# sensor_module_base.net
KiCad netlist of a schematic drawn in EAGLE
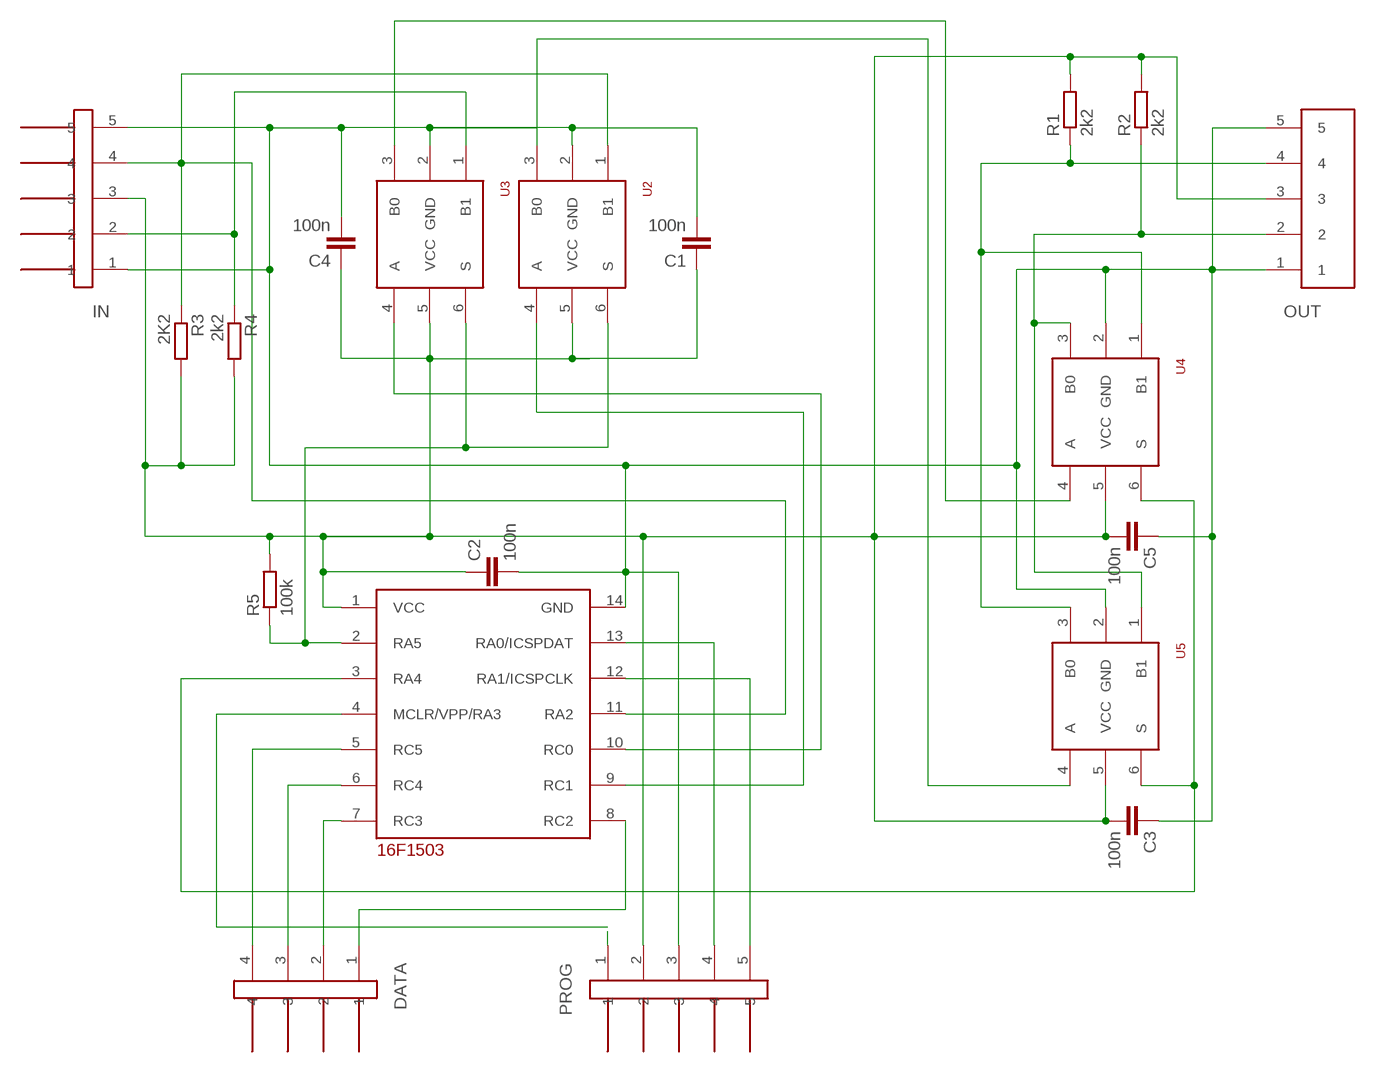
[diagram p0: schematic, sheet 1]

(export (version "E")
  (design (tool "Eeschema 10.0.6"))
  (components
    (comp (ref "C1")
      (value "100n")
      (footprint "eagle-import:C0603K")
      (libsource (lib "eagle-import") (part "C-EUC0603K"))
    )
    (comp (ref "C2")
      (value "100n")
      (footprint "eagle-import:C0603K")
      (libsource (lib "eagle-import") (part "C-EUC0603K"))
    )
    (comp (ref "C3")
      (value "100n")
      (footprint "eagle-import:C0603K")
      (libsource (lib "eagle-import") (part "C-EUC0603K"))
    )
    (comp (ref "C4")
      (value "100n")
      (footprint "eagle-import:C0603K")
      (libsource (lib "eagle-import") (part "C-EUC0603K"))
    )
    (comp (ref "C5")
      (value "100n")
      (footprint "eagle-import:C0603K")
      (libsource (lib "eagle-import") (part "C-EUC0603K"))
    )
    (comp (ref "DATA")
      (value "JUMPER4M")
      (footprint "eagle-import:JUMPER4M")
      (libsource (lib "eagle-import") (part "JUMPER4M"))
    )
    (comp (ref "IN")
      (value "JUMPER5M-90")
      (footprint "eagle-import:JUMPER5M-90")
      (libsource (lib "eagle-import") (part "JUMPER5M-90"))
    )
    (comp (ref "OUT")
      (value "JUMPER5F-90")
      (footprint "eagle-import:JUMPER5F-90")
      (libsource (lib "eagle-import") (part "JUMPER5F-90"))
    )
    (comp (ref "PROG")
      (value "JUMPER5M")
      (footprint "eagle-import:JUMPER5M")
      (libsource (lib "eagle-import") (part "JUMPER5M"))
    )
    (comp (ref "R1")
      (value "2k2")
      (footprint "eagle-import:R0603")
      (libsource (lib "eagle-import") (part "R-EU_R0603"))
    )
    (comp (ref "R2")
      (value "2k2")
      (footprint "eagle-import:R0603")
      (libsource (lib "eagle-import") (part "R-EU_R0603"))
    )
    (comp (ref "R3")
      (value "2K2")
      (footprint "eagle-import:R0603")
      (libsource (lib "eagle-import") (part "R-EU_R0603"))
    )
    (comp (ref "R4")
      (value "2k2")
      (footprint "eagle-import:R0603")
      (libsource (lib "eagle-import") (part "R-EU_R0603"))
    )
    (comp (ref "R5")
      (value "100k")
      (footprint "eagle-import:R0603")
      (libsource (lib "eagle-import") (part "R-EU_R0603"))
    )
    (comp (ref "U1")
      (value "16F103")
      (footprint "eagle-import:TSSOP14")
      (libsource (lib "eagle-import") (part "16F103-TSSOP"))
    )
    (comp (ref "U2")
      (value "NC7SB3157P6X")
      (footprint "eagle-import:SC70-6L")
      (libsource (lib "eagle-import") (part "NC7SB3157P6X"))
    )
    (comp (ref "U3")
      (value "NC7SB3157P6X")
      (footprint "eagle-import:SC70-6L")
      (libsource (lib "eagle-import") (part "NC7SB3157P6X"))
    )
    (comp (ref "U4")
      (value "NC7SB3157P6X")
      (footprint "eagle-import:SC70-6L")
      (libsource (lib "eagle-import") (part "NC7SB3157P6X"))
    )
    (comp (ref "U5")
      (value "NC7SB3157P6X")
      (footprint "eagle-import:SC70-6L")
      (libsource (lib "eagle-import") (part "NC7SB3157P6X"))
    )
  )
  (nets
    (net (code "1") (name "Net-(U1-GND)") (class "Default")
      (node (ref "C1") (pin "2") (pinfunction "2_2") (pintype "passive"))
      (node (ref "C2") (pin "2") (pinfunction "2_2") (pintype "passive"))
      (node (ref "C3") (pin "1") (pinfunction "1_1") (pintype "passive"))
      (node (ref "C4") (pin "2") (pinfunction "2_2") (pintype "passive"))
      (node (ref "C5") (pin "1") (pinfunction "1_1") (pintype "passive"))
      (node (ref "IN") (pin "1") (pinfunction "1_1") (pintype "bidirectional"))
      (node (ref "IN") (pin "5") (pinfunction "5_5") (pintype "bidirectional"))
      (node (ref "OUT") (pin "1") (pinfunction "1_1") (pintype "bidirectional"))
      (node (ref "OUT") (pin "5") (pinfunction "5_5") (pintype "bidirectional"))
      (node (ref "PROG") (pin "3") (pinfunction "3_3") (pintype "bidirectional"))
      (node (ref "U1") (pin "14") (pinfunction "GND_14") (pintype "power_in"))
      (node (ref "U2") (pin "2") (pinfunction "GND_2") (pintype "power_in"))
      (node (ref "U3") (pin "2") (pinfunction "GND_2") (pintype "power_in"))
      (node (ref "U4") (pin "2") (pinfunction "GND_2") (pintype "power_in"))
      (node (ref "U5") (pin "2") (pinfunction "GND_2") (pintype "power_in"))
    )
    (net (code "2") (name "Net-(U1-MCLR{slash}VPP{slash}RA3)") (class "Default")
      (node (ref "PROG") (pin "1") (pinfunction "1_1") (pintype "bidirectional"))
      (node (ref "U1") (pin "4") (pinfunction "MCLR/VPP/RA3_4") (pintype "bidirectional"))
    )
    (net (code "3") (name "Net-(U1-RA0{slash}ICSPDAT)") (class "Default")
      (node (ref "PROG") (pin "4") (pinfunction "4_4") (pintype "bidirectional"))
      (node (ref "U1") (pin "13") (pinfunction "RA0/ICSPDAT_13") (pintype "bidirectional"))
    )
    (net (code "4") (name "Net-(U1-RA1{slash}ICSPCLK)") (class "Default")
      (node (ref "PROG") (pin "5") (pinfunction "5_5") (pintype "bidirectional"))
      (node (ref "U1") (pin "12") (pinfunction "RA1/ICSPCLK_12") (pintype "bidirectional"))
    )
    (net (code "5") (name "Net-(U1-RA2)") (class "Default")
      (node (ref "IN") (pin "4") (pinfunction "4_4") (pintype "bidirectional"))
      (node (ref "R3") (pin "1") (pinfunction "1_1") (pintype "passive"))
      (node (ref "U1") (pin "11") (pinfunction "RA2_11") (pintype "bidirectional"))
      (node (ref "U2") (pin "1") (pinfunction "B1_1") (pintype "bidirectional"))
    )
    (net (code "6") (name "Net-(U1-RA4)") (class "Default")
      (node (ref "U1") (pin "3") (pinfunction "RA4_3") (pintype "bidirectional"))
      (node (ref "U4") (pin "6") (pinfunction "S_6") (pintype "bidirectional"))
      (node (ref "U5") (pin "6") (pinfunction "S_6") (pintype "bidirectional"))
    )
    (net (code "7") (name "Net-(U1-RA5)") (class "Default")
      (node (ref "R5") (pin "1") (pinfunction "1_1") (pintype "passive"))
      (node (ref "U1") (pin "2") (pinfunction "RA5_2") (pintype "bidirectional"))
      (node (ref "U2") (pin "6") (pinfunction "S_6") (pintype "bidirectional"))
      (node (ref "U3") (pin "6") (pinfunction "S_6") (pintype "bidirectional"))
    )
    (net (code "8") (name "Net-(U1-RC0)") (class "Default")
      (node (ref "U1") (pin "10") (pinfunction "RC0_10") (pintype "bidirectional"))
      (node (ref "U3") (pin "4") (pinfunction "A_4") (pintype "bidirectional"))
    )
    (net (code "9") (name "Net-(U1-RC1)") (class "Default")
      (node (ref "U1") (pin "9") (pinfunction "RC1_9") (pintype "bidirectional"))
      (node (ref "U2") (pin "4") (pinfunction "A_4") (pintype "bidirectional"))
    )
    (net (code "10") (name "Net-(U1-RC2)") (class "Default")
      (node (ref "DATA") (pin "1") (pinfunction "1_1") (pintype "bidirectional"))
      (node (ref "U1") (pin "8") (pinfunction "RC2_8") (pintype "bidirectional"))
    )
    (net (code "11") (name "Net-(U1-RC3)") (class "Default")
      (node (ref "DATA") (pin "2") (pinfunction "2_2") (pintype "bidirectional"))
      (node (ref "U1") (pin "7") (pinfunction "RC3_7") (pintype "bidirectional"))
    )
    (net (code "12") (name "Net-(U1-RC4)") (class "Default")
      (node (ref "DATA") (pin "3") (pinfunction "3_3") (pintype "bidirectional"))
      (node (ref "U1") (pin "6") (pinfunction "RC4_6") (pintype "bidirectional"))
    )
    (net (code "13") (name "Net-(U1-RC5)") (class "Default")
      (node (ref "DATA") (pin "4") (pinfunction "4_4") (pintype "bidirectional"))
      (node (ref "U1") (pin "5") (pinfunction "RC5_5") (pintype "bidirectional"))
    )
    (net (code "14") (name "Net-(U1-VCC)") (class "Default")
      (node (ref "C1") (pin "1") (pinfunction "1_1") (pintype "passive"))
      (node (ref "C2") (pin "1") (pinfunction "1_1") (pintype "passive"))
      (node (ref "C3") (pin "2") (pinfunction "2_2") (pintype "passive"))
      (node (ref "C4") (pin "1") (pinfunction "1_1") (pintype "passive"))
      (node (ref "C5") (pin "2") (pinfunction "2_2") (pintype "passive"))
      (node (ref "IN") (pin "3") (pinfunction "3_3") (pintype "bidirectional"))
      (node (ref "OUT") (pin "3") (pinfunction "3_3") (pintype "bidirectional"))
      (node (ref "PROG") (pin "2") (pinfunction "2_2") (pintype "bidirectional"))
      (node (ref "R1") (pin "2") (pinfunction "2_2") (pintype "passive"))
      (node (ref "R2") (pin "2") (pinfunction "2_2") (pintype "passive"))
      (node (ref "R3") (pin "2") (pinfunction "2_2") (pintype "passive"))
      (node (ref "R4") (pin "2") (pinfunction "2_2") (pintype "passive"))
      (node (ref "R5") (pin "2") (pinfunction "2_2") (pintype "passive"))
      (node (ref "U1") (pin "1") (pinfunction "VCC_1") (pintype "power_in"))
      (node (ref "U2") (pin "5") (pinfunction "VCC_5") (pintype "power_in"))
      (node (ref "U3") (pin "5") (pinfunction "VCC_5") (pintype "power_in"))
      (node (ref "U4") (pin "5") (pinfunction "VCC_5") (pintype "power_in"))
      (node (ref "U5") (pin "5") (pinfunction "VCC_5") (pintype "power_in"))
    )
    (net (code "15") (name "Net-(U2-B0)") (class "Default")
      (node (ref "U2") (pin "3") (pinfunction "B0_3") (pintype "bidirectional"))
      (node (ref "U5") (pin "4") (pinfunction "A_4") (pintype "bidirectional"))
    )
    (net (code "16") (name "Net-(U3-B0)") (class "Default")
      (node (ref "U3") (pin "3") (pinfunction "B0_3") (pintype "bidirectional"))
      (node (ref "U4") (pin "4") (pinfunction "A_4") (pintype "bidirectional"))
    )
    (net (code "17") (name "Net-(U3-B1)") (class "Default")
      (node (ref "IN") (pin "2") (pinfunction "2_2") (pintype "bidirectional"))
      (node (ref "R4") (pin "1") (pinfunction "1_1") (pintype "passive"))
      (node (ref "U3") (pin "1") (pinfunction "B1_1") (pintype "bidirectional"))
    )
    (net (code "18") (name "Net-(U4-B0)") (class "Default")
      (node (ref "OUT") (pin "2") (pinfunction "2_2") (pintype "bidirectional"))
      (node (ref "R2") (pin "1") (pinfunction "1_1") (pintype "passive"))
      (node (ref "U4") (pin "3") (pinfunction "B0_3") (pintype "bidirectional"))
      (node (ref "U5") (pin "1") (pinfunction "B1_1") (pintype "bidirectional"))
    )
    (net (code "19") (name "Net-(U4-B1)") (class "Default")
      (node (ref "OUT") (pin "4") (pinfunction "4_4") (pintype "bidirectional"))
      (node (ref "R1") (pin "1") (pinfunction "1_1") (pintype "passive"))
      (node (ref "U4") (pin "1") (pinfunction "B1_1") (pintype "bidirectional"))
      (node (ref "U5") (pin "3") (pinfunction "B0_3") (pintype "bidirectional"))
    )
  )
)
